# Schematic1_2023-10-10.net
KiCad netlist of a schematic drawn in EasyEDA Pro
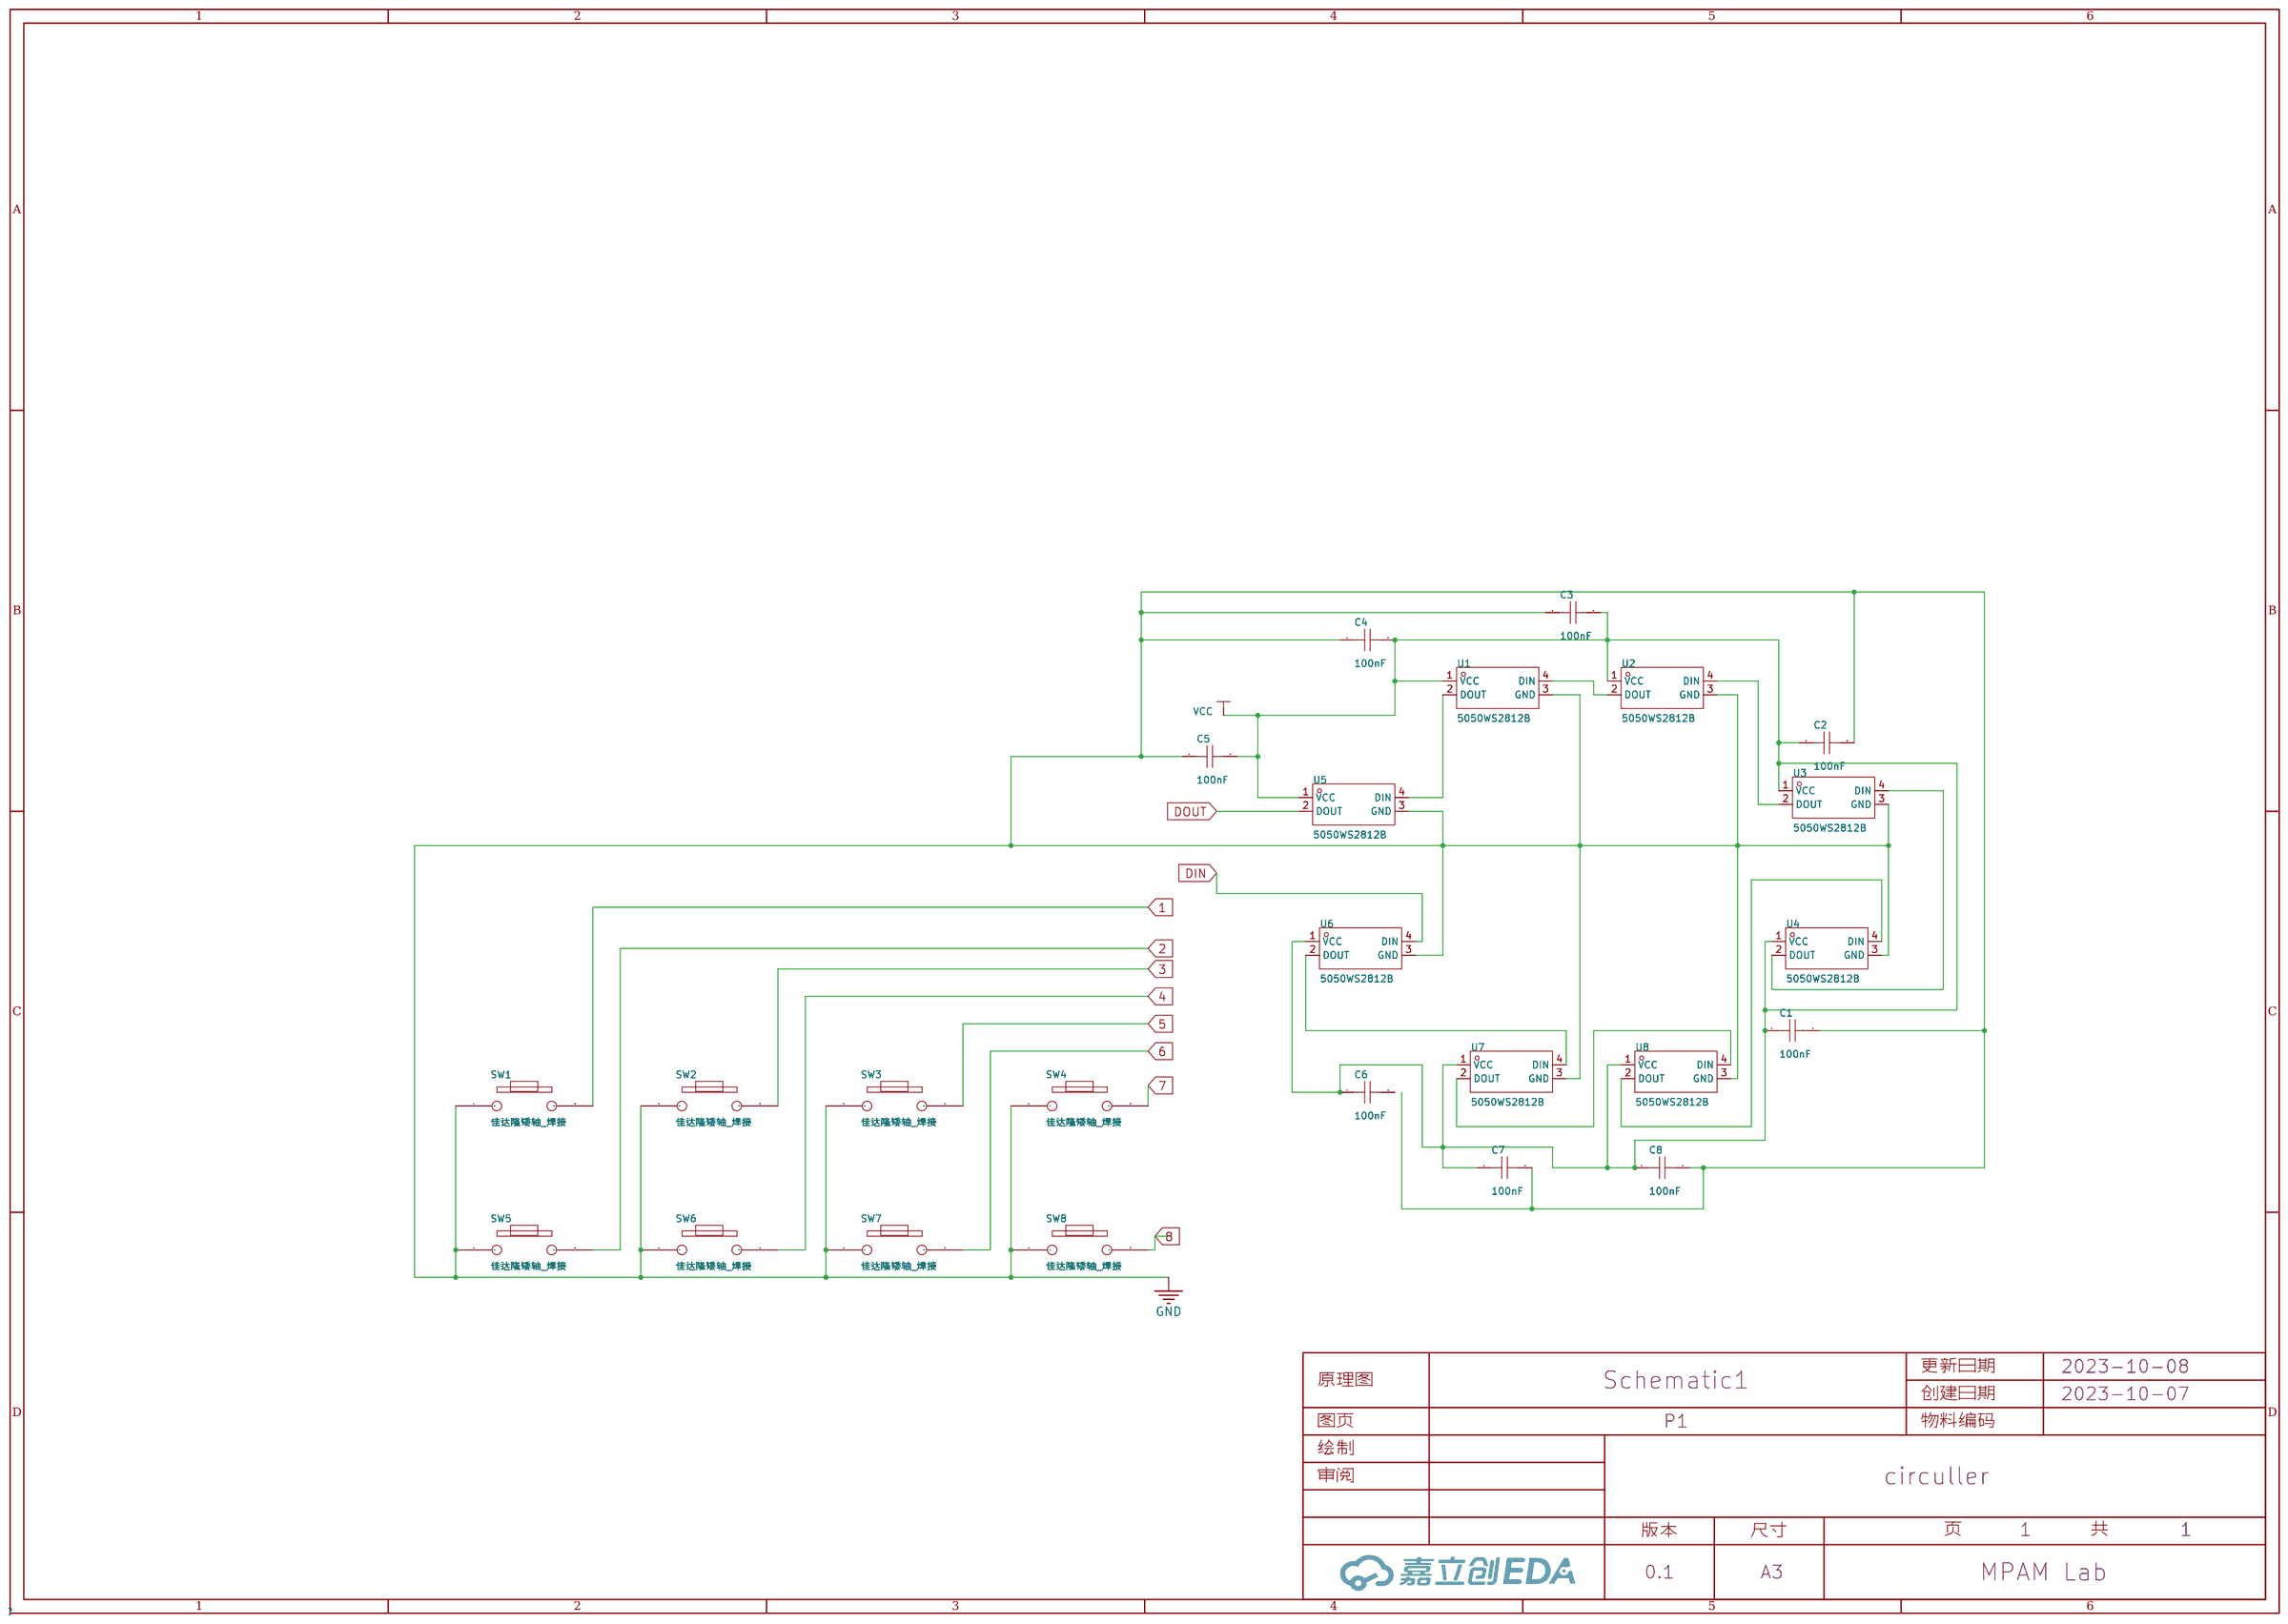
[diagram p0: schematic sheet]

(export (version "E")
  (design (tool "Eeschema 10.0.6"))
  (components
    (comp (ref "C1")
      (value "100nF")
      (footprint "easyedapro:C0603")
      (libsource (lib "easyedapro") (part "CapAcitance"))
    )
    (comp (ref "C2")
      (value "100nF")
      (footprint "easyedapro:C0603")
      (libsource (lib "easyedapro") (part "CapAcitance"))
    )
    (comp (ref "C3")
      (value "100nF")
      (footprint "easyedapro:C0603")
      (libsource (lib "easyedapro") (part "CapAcitance"))
    )
    (comp (ref "C4")
      (value "100nF")
      (footprint "easyedapro:C0603")
      (libsource (lib "easyedapro") (part "CapAcitance"))
    )
    (comp (ref "C5")
      (value "100nF")
      (footprint "easyedapro:C0603")
      (libsource (lib "easyedapro") (part "CapAcitance"))
    )
    (comp (ref "C6")
      (value "100nF")
      (footprint "easyedapro:C0603")
      (libsource (lib "easyedapro") (part "CapAcitance"))
    )
    (comp (ref "C7")
      (value "100nF")
      (footprint "easyedapro:C0603")
      (libsource (lib "easyedapro") (part "CapAcitance"))
    )
    (comp (ref "C8")
      (value "100nF")
      (footprint "easyedapro:C0603")
      (libsource (lib "easyedapro") (part "CapAcitance"))
    )
    (comp (ref "SW1") (value "佳达隆矮轴_焊接") (libsource (lib "easyedapro") (part "佳达隆矮轴_焊接")))
    (comp (ref "SW2") (value "佳达隆矮轴_焊接") (libsource (lib "easyedapro") (part "佳达隆矮轴_焊接")))
    (comp (ref "SW3") (value "佳达隆矮轴_焊接") (libsource (lib "easyedapro") (part "佳达隆矮轴_焊接")))
    (comp (ref "SW4") (value "佳达隆矮轴_焊接") (libsource (lib "easyedapro") (part "佳达隆矮轴_焊接")))
    (comp (ref "SW5") (value "佳达隆矮轴_焊接") (libsource (lib "easyedapro") (part "佳达隆矮轴_焊接")))
    (comp (ref "SW6") (value "佳达隆矮轴_焊接") (libsource (lib "easyedapro") (part "佳达隆矮轴_焊接")))
    (comp (ref "SW7") (value "佳达隆矮轴_焊接") (libsource (lib "easyedapro") (part "佳达隆矮轴_焊接")))
    (comp (ref "SW8") (value "佳达隆矮轴_焊接") (libsource (lib "easyedapro") (part "佳达隆矮轴_焊接")))
    (comp (ref "U1")
      (value "5050WS2812B")
      (footprint "easyedapro:LED-SMD_5050WS2812B")
      (libsource (lib "easyedapro") (part "5050WS2812B"))
    )
    (comp (ref "U2")
      (value "5050WS2812B")
      (footprint "easyedapro:LED-SMD_5050WS2812B")
      (libsource (lib "easyedapro") (part "5050WS2812B"))
    )
    (comp (ref "U3")
      (value "5050WS2812B")
      (footprint "easyedapro:LED-SMD_5050WS2812B")
      (libsource (lib "easyedapro") (part "5050WS2812B"))
    )
    (comp (ref "U4")
      (value "5050WS2812B")
      (footprint "easyedapro:LED-SMD_5050WS2812B")
      (libsource (lib "easyedapro") (part "5050WS2812B"))
    )
    (comp (ref "U5")
      (value "5050WS2812B")
      (footprint "easyedapro:LED-SMD_5050WS2812B")
      (libsource (lib "easyedapro") (part "5050WS2812B"))
    )
    (comp (ref "U6")
      (value "5050WS2812B")
      (footprint "easyedapro:LED-SMD_5050WS2812B")
      (libsource (lib "easyedapro") (part "5050WS2812B"))
    )
    (comp (ref "U7")
      (value "5050WS2812B")
      (footprint "easyedapro:LED-SMD_5050WS2812B")
      (libsource (lib "easyedapro") (part "5050WS2812B"))
    )
    (comp (ref "U8")
      (value "5050WS2812B")
      (footprint "easyedapro:LED-SMD_5050WS2812B")
      (libsource (lib "easyedapro") (part "5050WS2812B"))
    )
  )
  (nets
    (net (code "1") (name "1") (class "Default")
      (node (ref "SW1") (pin "2") (pinfunction "2_2") (pintype "input"))
    )
    (net (code "2") (name "2") (class "Default")
      (node (ref "SW5") (pin "2") (pinfunction "2_2") (pintype "input"))
    )
    (net (code "3") (name "3") (class "Default")
      (node (ref "SW2") (pin "2") (pinfunction "2_2") (pintype "input"))
    )
    (net (code "4") (name "4") (class "Default")
      (node (ref "SW6") (pin "2") (pinfunction "2_2") (pintype "input"))
    )
    (net (code "5") (name "5") (class "Default")
      (node (ref "SW3") (pin "2") (pinfunction "2_2") (pintype "input"))
    )
    (net (code "6") (name "6") (class "Default")
      (node (ref "SW7") (pin "2") (pinfunction "2_2") (pintype "input"))
    )
    (net (code "7") (name "7") (class "Default")
      (node (ref "SW4") (pin "2") (pinfunction "2_2") (pintype "input"))
    )
    (net (code "8") (name "8") (class "Default")
      (node (ref "SW8") (pin "2") (pinfunction "2_2") (pintype "input"))
    )
    (net (code "9") (name "DIN") (class "Default")
      (node (ref "U6") (pin "4") (pinfunction "DIN_4") (pintype "input"))
    )
    (net (code "10") (name "DOUT") (class "Default")
      (node (ref "U5") (pin "2") (pinfunction "DOUT_2") (pintype "input"))
    )
    (net (code "11") (name "GND") (class "Default")
      (node (ref "C1") (pin "2") (pinfunction "2_2") (pintype "input"))
      (node (ref "C2") (pin "2") (pinfunction "2_2") (pintype "input"))
      (node (ref "C3") (pin "1") (pinfunction "1_1") (pintype "input"))
      (node (ref "C4") (pin "1") (pinfunction "1_1") (pintype "input"))
      (node (ref "C5") (pin "1") (pinfunction "1_1") (pintype "input"))
      (node (ref "C7") (pin "2") (pinfunction "2_2") (pintype "input"))
      (node (ref "C8") (pin "2") (pinfunction "2_2") (pintype "input"))
      (node (ref "SW1") (pin "1") (pinfunction "1_1") (pintype "input"))
      (node (ref "SW2") (pin "1") (pinfunction "1_1") (pintype "input"))
      (node (ref "SW3") (pin "1") (pinfunction "1_1") (pintype "input"))
      (node (ref "SW4") (pin "1") (pinfunction "1_1") (pintype "input"))
      (node (ref "SW5") (pin "1") (pinfunction "1_1") (pintype "input"))
      (node (ref "SW6") (pin "1") (pinfunction "1_1") (pintype "input"))
      (node (ref "SW7") (pin "1") (pinfunction "1_1") (pintype "input"))
      (node (ref "SW8") (pin "1") (pinfunction "1_1") (pintype "input"))
      (node (ref "U1") (pin "3") (pinfunction "GND_3") (pintype "input"))
      (node (ref "U2") (pin "3") (pinfunction "GND_3") (pintype "input"))
      (node (ref "U3") (pin "3") (pinfunction "GND_3") (pintype "input"))
      (node (ref "U4") (pin "3") (pinfunction "GND_3") (pintype "input"))
      (node (ref "U5") (pin "3") (pinfunction "GND_3") (pintype "input"))
      (node (ref "U6") (pin "3") (pinfunction "GND_3") (pintype "input"))
      (node (ref "U7") (pin "3") (pinfunction "GND_3") (pintype "input"))
      (node (ref "U8") (pin "3") (pinfunction "GND_3") (pintype "input"))
    )
    (net (code "12") (name "Net-(U1-DIN)") (class "Default")
      (node (ref "U1") (pin "4") (pinfunction "DIN_4") (pintype "input"))
      (node (ref "U2") (pin "2") (pinfunction "DOUT_2") (pintype "input"))
    )
    (net (code "13") (name "Net-(U1-DOUT)") (class "Default")
      (node (ref "U1") (pin "2") (pinfunction "DOUT_2") (pintype "input"))
      (node (ref "U5") (pin "4") (pinfunction "DIN_4") (pintype "input"))
    )
    (net (code "14") (name "Net-(U2-DIN)") (class "Default")
      (node (ref "U2") (pin "4") (pinfunction "DIN_4") (pintype "input"))
      (node (ref "U3") (pin "2") (pinfunction "DOUT_2") (pintype "input"))
    )
    (net (code "15") (name "Net-(U3-DIN)") (class "Default")
      (node (ref "U3") (pin "4") (pinfunction "DIN_4") (pintype "input"))
      (node (ref "U4") (pin "2") (pinfunction "DOUT_2") (pintype "input"))
    )
    (net (code "16") (name "Net-(U4-DIN)") (class "Default")
      (node (ref "U4") (pin "4") (pinfunction "DIN_4") (pintype "input"))
      (node (ref "U8") (pin "2") (pinfunction "DOUT_2") (pintype "input"))
    )
    (net (code "17") (name "Net-(U6-DOUT)") (class "Default")
      (node (ref "U6") (pin "2") (pinfunction "DOUT_2") (pintype "input"))
      (node (ref "U7") (pin "4") (pinfunction "DIN_4") (pintype "input"))
    )
    (net (code "18") (name "Net-(U7-DOUT)") (class "Default")
      (node (ref "U7") (pin "2") (pinfunction "DOUT_2") (pintype "input"))
      (node (ref "U8") (pin "4") (pinfunction "DIN_4") (pintype "input"))
    )
    (net (code "19") (name "VCC") (class "Default")
      (node (ref "C1") (pin "1") (pinfunction "1_1") (pintype "input"))
      (node (ref "C2") (pin "1") (pinfunction "1_1") (pintype "input"))
      (node (ref "C3") (pin "2") (pinfunction "2_2") (pintype "input"))
      (node (ref "C4") (pin "2") (pinfunction "2_2") (pintype "input"))
      (node (ref "C5") (pin "2") (pinfunction "2_2") (pintype "input"))
      (node (ref "C6") (pin "1") (pinfunction "1_1") (pintype "input"))
      (node (ref "C7") (pin "1") (pinfunction "1_1") (pintype "input"))
      (node (ref "C8") (pin "1") (pinfunction "1_1") (pintype "input"))
      (node (ref "U1") (pin "1") (pinfunction "VCC_1") (pintype "input"))
      (node (ref "U2") (pin "1") (pinfunction "VCC_1") (pintype "input"))
      (node (ref "U3") (pin "1") (pinfunction "VCC_1") (pintype "input"))
      (node (ref "U4") (pin "1") (pinfunction "VCC_1") (pintype "input"))
      (node (ref "U5") (pin "1") (pinfunction "VCC_1") (pintype "input"))
      (node (ref "U6") (pin "1") (pinfunction "VCC_1") (pintype "input"))
      (node (ref "U7") (pin "1") (pinfunction "VCC_1") (pintype "input"))
      (node (ref "U8") (pin "1") (pinfunction "VCC_1") (pintype "input"))
    )
    (net (code "20") (name "unconnected-(C6-Pad2)") (class "Default")
      (node (ref "C6") (pin "2") (pinfunction "2_2") (pintype "input"))
    )
  )
)
